# schemat.net
KiCad netlist of a schematic drawn in EAGLE
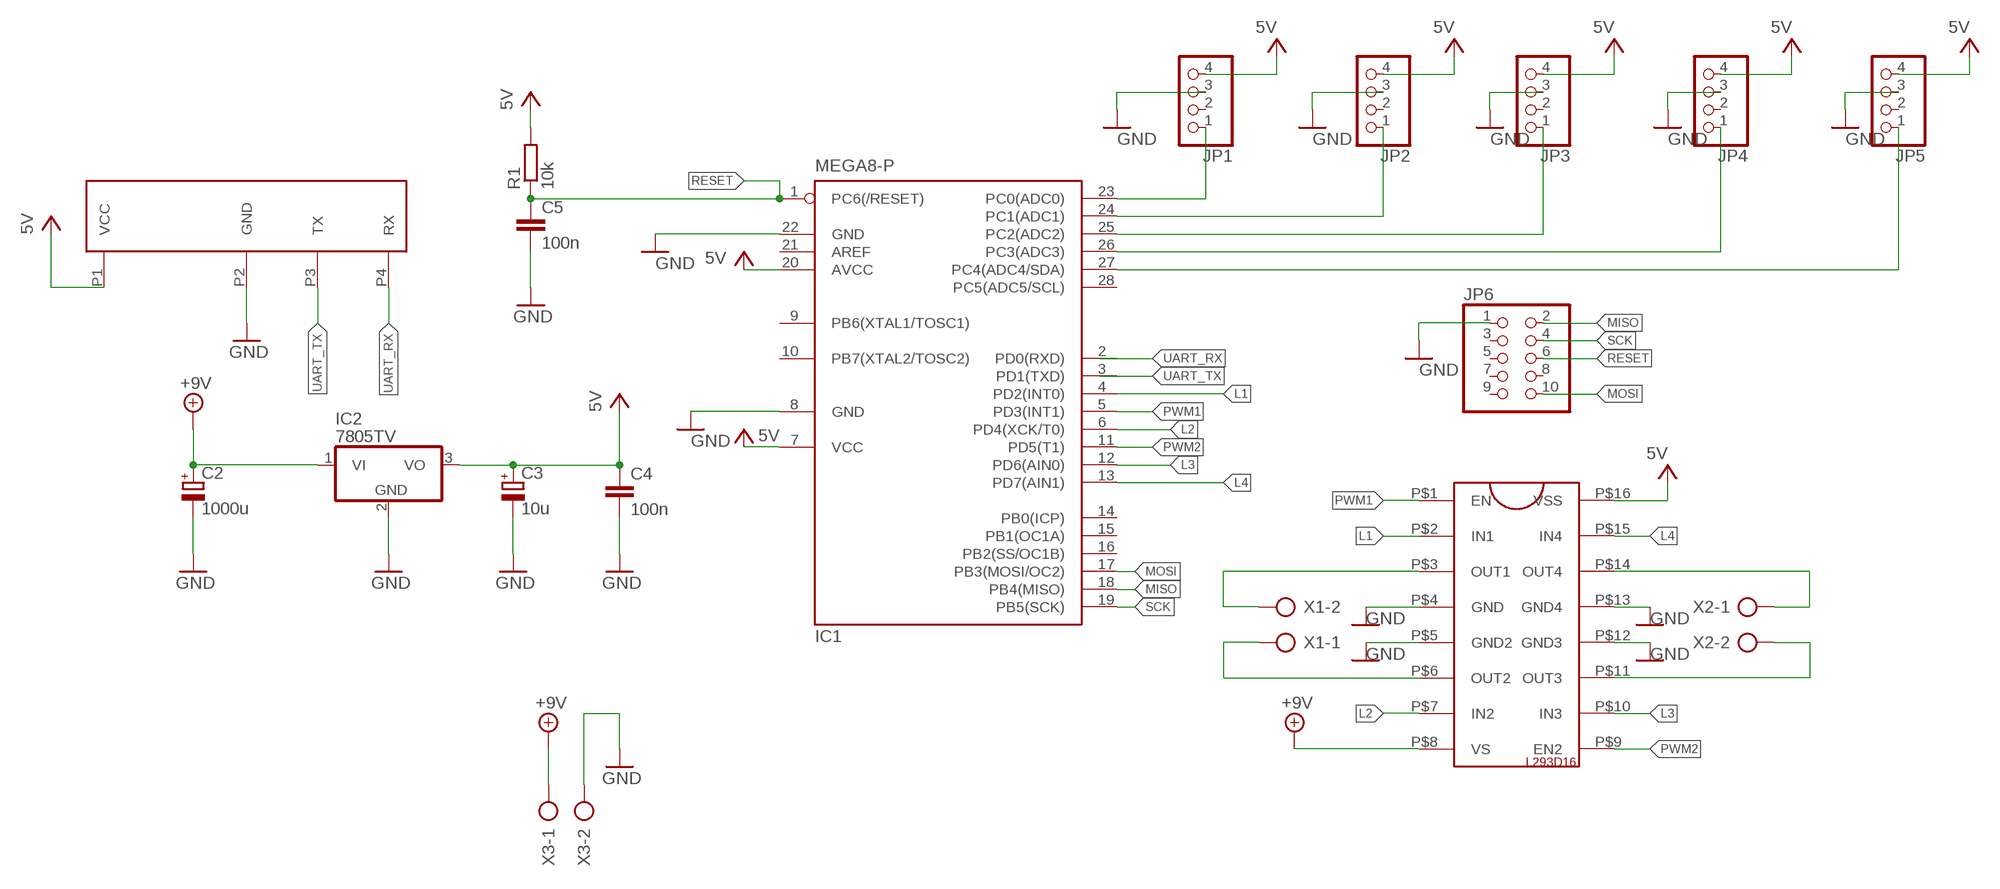
[diagram p0: schematic, sheet 1]

(export (version "E")
  (design (tool "Eeschema 10.0.6"))
  (components
    (comp (ref "C2")
      (value "1000u")
      (footprint "eagle-import:E5-10,5")
      (libsource (lib "eagle-import") (part "CPOL-EUE5-10.5"))
    )
    (comp (ref "C3")
      (value "10u")
      (footprint "eagle-import:E5-10,5")
      (libsource (lib "eagle-import") (part "CPOL-EUE5-10.5"))
    )
    (comp (ref "C4")
      (value "100n")
      (footprint "eagle-import:C050-075X075")
      (libsource (lib "eagle-import") (part "C-EU050-075X075"))
    )
    (comp (ref "C5")
      (value "100n")
      (footprint "eagle-import:C050-075X075")
      (libsource (lib "eagle-import") (part "C-EU050-075X075"))
    )
    (comp (ref "IC1")
      (value "MEGA8-P")
      (footprint "eagle-import:DIL28-3")
      (libsource (lib "eagle-import") (part "MEGA8-P"))
    )
    (comp (ref "IC2")
      (value "7805TV")
      (footprint "eagle-import:TO220V")
      (libsource (lib "eagle-import") (part "78TV05"))
    )
    (comp (ref "JP1")
      (value "PINHD-1X4/90")
      (footprint "eagle-import:1X04_90")
      (libsource (lib "eagle-import") (part "PINHD-1X4/90"))
    )
    (comp (ref "JP2")
      (value "PINHD-1X4/90")
      (footprint "eagle-import:1X04_90")
      (libsource (lib "eagle-import") (part "PINHD-1X4/90"))
    )
    (comp (ref "JP3")
      (value "PINHD-1X4/90")
      (footprint "eagle-import:1X04_90")
      (libsource (lib "eagle-import") (part "PINHD-1X4/90"))
    )
    (comp (ref "JP4")
      (value "PINHD-1X4/90")
      (footprint "eagle-import:1X04_90")
      (libsource (lib "eagle-import") (part "PINHD-1X4/90"))
    )
    (comp (ref "JP5")
      (value "PINHD-1X4/90")
      (footprint "eagle-import:1X04_90")
      (libsource (lib "eagle-import") (part "PINHD-1X4/90"))
    )
    (comp (ref "JP6")
      (value "PINHD-2X5")
      (footprint "eagle-import:2X05")
      (libsource (lib "eagle-import") (part "PINHD-2X5"))
    )
    (comp (ref "R1")
      (value "10k")
      (footprint "eagle-import:0309_10")
      (libsource (lib "eagle-import") (part "R-EU_0309/10"))
    )
    (comp (ref "U$1")
      (value "BTM222BTM222")
      (footprint "eagle-import:BTM222")
      (libsource (lib "eagle-import") (part "BTM222BTM222"))
    )
    (comp (ref "U$2")
      (value "L293D16L293D16")
      (footprint "eagle-import:L293D")
      (libsource (lib "eagle-import") (part "L293D16L293D16"))
    )
    (comp (ref "X1")
      (value "AK500/2")
      (footprint "eagle-import:AK500_2")
      (libsource (lib "eagle-import") (part "AK500/2"))
    )
    (comp (ref "X2")
      (value "AK500/2")
      (footprint "eagle-import:AK500_2")
      (libsource (lib "eagle-import") (part "AK500/2"))
    )
    (comp (ref "X3")
      (value "AK500/2")
      (footprint "eagle-import:AK500_2")
      (libsource (lib "eagle-import") (part "AK500/2"))
    )
  )
  (nets
    (net (code "1") (name "+9V") (class "Default")
      (node (ref "C2") (pin "+") (pinfunction "+_+") (pintype "passive"))
      (node (ref "IC2") (pin "1") (pinfunction "VI_1") (pintype "input"))
      (node (ref "U$2") (pin "P$8") (pinfunction "VS_P$8") (pintype "bidirectional"))
      (node (ref "X3") (pin "1") (pinfunction "KL_1") (pintype "passive"))
    )
    (net (code "2") (name "5V") (class "Default")
      (node (ref "C3") (pin "+") (pinfunction "+_+") (pintype "passive"))
      (node (ref "C4") (pin "1") (pinfunction "1_1") (pintype "passive"))
      (node (ref "IC1") (pin "20") (pinfunction "AVCC_20") (pintype "power_in"))
      (node (ref "IC1") (pin "7") (pinfunction "VCC_7") (pintype "power_in"))
      (node (ref "IC2") (pin "3") (pinfunction "VO_3") (pintype "passive"))
      (node (ref "JP1") (pin "4") (pinfunction "4_4") (pintype "passive"))
      (node (ref "JP2") (pin "4") (pinfunction "4_4") (pintype "passive"))
      (node (ref "JP3") (pin "4") (pinfunction "4_4") (pintype "passive"))
      (node (ref "JP4") (pin "4") (pinfunction "4_4") (pintype "passive"))
      (node (ref "JP5") (pin "4") (pinfunction "4_4") (pintype "passive"))
      (node (ref "R1") (pin "2") (pinfunction "2_2") (pintype "passive"))
      (node (ref "U$1") (pin "P1") (pinfunction "VCC_P1") (pintype "bidirectional"))
      (node (ref "U$2") (pin "P$16") (pinfunction "VSS_P$16") (pintype "bidirectional"))
    )
    (net (code "3") (name "GND") (class "Default")
      (node (ref "C2") (pin "-") (pinfunction "-_-") (pintype "passive"))
      (node (ref "C3") (pin "-") (pinfunction "-_-") (pintype "passive"))
      (node (ref "C4") (pin "2") (pinfunction "2_2") (pintype "passive"))
      (node (ref "C5") (pin "2") (pinfunction "2_2") (pintype "passive"))
      (node (ref "IC1") (pin "22") (pinfunction "GND_22") (pintype "power_in"))
      (node (ref "IC1") (pin "8") (pinfunction "GND_8") (pintype "power_in"))
      (node (ref "IC2") (pin "2") (pinfunction "GND_2") (pintype "passive"))
      (node (ref "JP1") (pin "3") (pinfunction "3_3") (pintype "passive"))
      (node (ref "JP2") (pin "3") (pinfunction "3_3") (pintype "passive"))
      (node (ref "JP3") (pin "3") (pinfunction "3_3") (pintype "passive"))
      (node (ref "JP4") (pin "3") (pinfunction "3_3") (pintype "passive"))
      (node (ref "JP5") (pin "3") (pinfunction "3_3") (pintype "passive"))
      (node (ref "JP6") (pin "1") (pinfunction "1_1") (pintype "passive"))
      (node (ref "U$1") (pin "P2") (pinfunction "GND_P2") (pintype "bidirectional"))
      (node (ref "U$2") (pin "P$12") (pinfunction "GND3_P$12") (pintype "bidirectional"))
      (node (ref "U$2") (pin "P$13") (pinfunction "GND4_P$13") (pintype "bidirectional"))
      (node (ref "U$2") (pin "P$4") (pinfunction "GND_P$4") (pintype "bidirectional"))
      (node (ref "U$2") (pin "P$5") (pinfunction "GND2_P$5") (pintype "bidirectional"))
      (node (ref "X3") (pin "2") (pinfunction "KL_2") (pintype "passive"))
    )
    (net (code "4") (name "L1") (class "Default")
      (node (ref "IC1") (pin "4") (pinfunction "PD2(INT0)_4") (pintype "bidirectional"))
      (node (ref "U$2") (pin "P$2") (pinfunction "IN1_P$2") (pintype "bidirectional"))
    )
    (net (code "5") (name "L2") (class "Default")
      (node (ref "IC1") (pin "6") (pinfunction "PD4(XCK/T0)_6") (pintype "bidirectional"))
      (node (ref "U$2") (pin "P$7") (pinfunction "IN2_P$7") (pintype "bidirectional"))
    )
    (net (code "6") (name "L3") (class "Default")
      (node (ref "IC1") (pin "12") (pinfunction "PD6(AIN0)_12") (pintype "bidirectional"))
      (node (ref "U$2") (pin "P$10") (pinfunction "IN3_P$10") (pintype "bidirectional"))
    )
    (net (code "7") (name "L4") (class "Default")
      (node (ref "IC1") (pin "13") (pinfunction "PD7(AIN1)_13") (pintype "bidirectional"))
      (node (ref "U$2") (pin "P$15") (pinfunction "IN4_P$15") (pintype "bidirectional"))
    )
    (net (code "8") (name "MISO") (class "Default")
      (node (ref "IC1") (pin "18") (pinfunction "PB4(MISO)_18") (pintype "bidirectional"))
      (node (ref "JP6") (pin "2") (pinfunction "2_2") (pintype "passive"))
    )
    (net (code "9") (name "MOSI") (class "Default")
      (node (ref "IC1") (pin "17") (pinfunction "PB3(MOSI/OC2)_17") (pintype "bidirectional"))
      (node (ref "JP6") (pin "10") (pinfunction "10_10") (pintype "passive"))
    )
    (net (code "10") (name "Net-(IC1-PC0(ADC0))") (class "Default")
      (node (ref "IC1") (pin "23") (pinfunction "PC0(ADC0)_23") (pintype "bidirectional"))
      (node (ref "JP1") (pin "1") (pinfunction "1_1") (pintype "passive"))
    )
    (net (code "11") (name "Net-(IC1-PC1(ADC1))") (class "Default")
      (node (ref "IC1") (pin "24") (pinfunction "PC1(ADC1)_24") (pintype "bidirectional"))
      (node (ref "JP2") (pin "1") (pinfunction "1_1") (pintype "passive"))
    )
    (net (code "12") (name "Net-(IC1-PC2(ADC2))") (class "Default")
      (node (ref "IC1") (pin "25") (pinfunction "PC2(ADC2)_25") (pintype "bidirectional"))
      (node (ref "JP3") (pin "1") (pinfunction "1_1") (pintype "passive"))
    )
    (net (code "13") (name "Net-(IC1-PC3(ADC3))") (class "Default")
      (node (ref "IC1") (pin "26") (pinfunction "PC3(ADC3)_26") (pintype "bidirectional"))
      (node (ref "JP4") (pin "1") (pinfunction "1_1") (pintype "passive"))
    )
    (net (code "14") (name "Net-(IC1-PC4(ADC4{slash}SDA))") (class "Default")
      (node (ref "IC1") (pin "27") (pinfunction "PC4(ADC4/SDA)_27") (pintype "bidirectional"))
      (node (ref "JP5") (pin "1") (pinfunction "1_1") (pintype "passive"))
    )
    (net (code "15") (name "Net-(U$2-OUT1)") (class "Default")
      (node (ref "U$2") (pin "P$3") (pinfunction "OUT1_P$3") (pintype "bidirectional"))
      (node (ref "X1") (pin "2") (pinfunction "KL_2") (pintype "passive"))
    )
    (net (code "16") (name "Net-(U$2-OUT2)") (class "Default")
      (node (ref "U$2") (pin "P$6") (pinfunction "OUT2_P$6") (pintype "bidirectional"))
      (node (ref "X1") (pin "1") (pinfunction "KL_1") (pintype "passive"))
    )
    (net (code "17") (name "Net-(U$2-OUT3)") (class "Default")
      (node (ref "U$2") (pin "P$11") (pinfunction "OUT3_P$11") (pintype "bidirectional"))
      (node (ref "X2") (pin "2") (pinfunction "KL_2") (pintype "passive"))
    )
    (net (code "18") (name "Net-(U$2-OUT4)") (class "Default")
      (node (ref "U$2") (pin "P$14") (pinfunction "OUT4_P$14") (pintype "bidirectional"))
      (node (ref "X2") (pin "1") (pinfunction "KL_1") (pintype "passive"))
    )
    (net (code "19") (name "PWM1") (class "Default")
      (node (ref "IC1") (pin "5") (pinfunction "PD3(INT1)_5") (pintype "bidirectional"))
      (node (ref "U$2") (pin "P$1") (pinfunction "EN_P$1") (pintype "bidirectional"))
    )
    (net (code "20") (name "PWM2") (class "Default")
      (node (ref "IC1") (pin "11") (pinfunction "PD5(T1)_11") (pintype "bidirectional"))
      (node (ref "U$2") (pin "P$9") (pinfunction "EN2_P$9") (pintype "bidirectional"))
    )
    (net (code "21") (name "RESET") (class "Default")
      (node (ref "C5") (pin "1") (pinfunction "1_1") (pintype "passive"))
      (node (ref "IC1") (pin "1") (pinfunction "PC6(/RESET)_1") (pintype "bidirectional"))
      (node (ref "JP6") (pin "6") (pinfunction "6_6") (pintype "passive"))
      (node (ref "R1") (pin "1") (pinfunction "1_1") (pintype "passive"))
    )
    (net (code "22") (name "SCK") (class "Default")
      (node (ref "IC1") (pin "19") (pinfunction "PB5(SCK)_19") (pintype "bidirectional"))
      (node (ref "JP6") (pin "4") (pinfunction "4_4") (pintype "passive"))
    )
    (net (code "23") (name "UART_RX") (class "Default")
      (node (ref "IC1") (pin "2") (pinfunction "PD0(RXD)_2") (pintype "bidirectional"))
      (node (ref "U$1") (pin "P4") (pinfunction "RX_P4") (pintype "bidirectional"))
    )
    (net (code "24") (name "UART_TX") (class "Default")
      (node (ref "IC1") (pin "3") (pinfunction "PD1(TXD)_3") (pintype "bidirectional"))
      (node (ref "U$1") (pin "P3") (pinfunction "TX_P3") (pintype "bidirectional"))
    )
    (net (code "25") (name "unconnected-(IC1-AREF-Pad21)") (class "Default")
      (node (ref "IC1") (pin "21") (pinfunction "AREF_21") (pintype "passive"))
    )
    (net (code "26") (name "unconnected-(IC1-PB0(ICP)-Pad14)") (class "Default")
      (node (ref "IC1") (pin "14") (pinfunction "PB0(ICP)_14") (pintype "bidirectional"))
    )
    (net (code "27") (name "unconnected-(IC1-PB1(OC1A)-Pad15)") (class "Default")
      (node (ref "IC1") (pin "15") (pinfunction "PB1(OC1A)_15") (pintype "bidirectional"))
    )
    (net (code "28") (name "unconnected-(IC1-PB2(SS{slash}OC1B)-Pad16)") (class "Default")
      (node (ref "IC1") (pin "16") (pinfunction "PB2(SS/OC1B)_16") (pintype "bidirectional"))
    )
    (net (code "29") (name "unconnected-(IC1-PB6(XTAL1{slash}TOSC1)-Pad9)") (class "Default")
      (node (ref "IC1") (pin "9") (pinfunction "PB6(XTAL1/TOSC1)_9") (pintype "bidirectional"))
    )
    (net (code "30") (name "unconnected-(IC1-PB7(XTAL2{slash}TOSC2)-Pad10)") (class "Default")
      (node (ref "IC1") (pin "10") (pinfunction "PB7(XTAL2/TOSC2)_10") (pintype "bidirectional"))
    )
    (net (code "31") (name "unconnected-(IC1-PC5(ADC5{slash}SCL)-Pad28)") (class "Default")
      (node (ref "IC1") (pin "28") (pinfunction "PC5(ADC5/SCL)_28") (pintype "bidirectional"))
    )
    (net (code "32") (name "unconnected-(JP1-Pad2)") (class "Default")
      (node (ref "JP1") (pin "2") (pinfunction "2_2") (pintype "passive"))
    )
    (net (code "33") (name "unconnected-(JP2-Pad2)") (class "Default")
      (node (ref "JP2") (pin "2") (pinfunction "2_2") (pintype "passive"))
    )
    (net (code "34") (name "unconnected-(JP3-Pad2)") (class "Default")
      (node (ref "JP3") (pin "2") (pinfunction "2_2") (pintype "passive"))
    )
    (net (code "35") (name "unconnected-(JP4-Pad2)") (class "Default")
      (node (ref "JP4") (pin "2") (pinfunction "2_2") (pintype "passive"))
    )
    (net (code "36") (name "unconnected-(JP5-Pad2)") (class "Default")
      (node (ref "JP5") (pin "2") (pinfunction "2_2") (pintype "passive"))
    )
    (net (code "37") (name "unconnected-(JP6-Pad3)") (class "Default")
      (node (ref "JP6") (pin "3") (pinfunction "3_3") (pintype "passive"))
    )
    (net (code "38") (name "unconnected-(JP6-Pad5)") (class "Default")
      (node (ref "JP6") (pin "5") (pinfunction "5_5") (pintype "passive"))
    )
    (net (code "39") (name "unconnected-(JP6-Pad7)") (class "Default")
      (node (ref "JP6") (pin "7") (pinfunction "7_7") (pintype "passive"))
    )
    (net (code "40") (name "unconnected-(JP6-Pad8)") (class "Default")
      (node (ref "JP6") (pin "8") (pinfunction "8_8") (pintype "passive"))
    )
    (net (code "41") (name "unconnected-(JP6-Pad9)") (class "Default")
      (node (ref "JP6") (pin "9") (pinfunction "9_9") (pintype "passive"))
    )
  )
)
